# Sheet2.net
KiCad netlist of a schematic drawn in Altium Designer
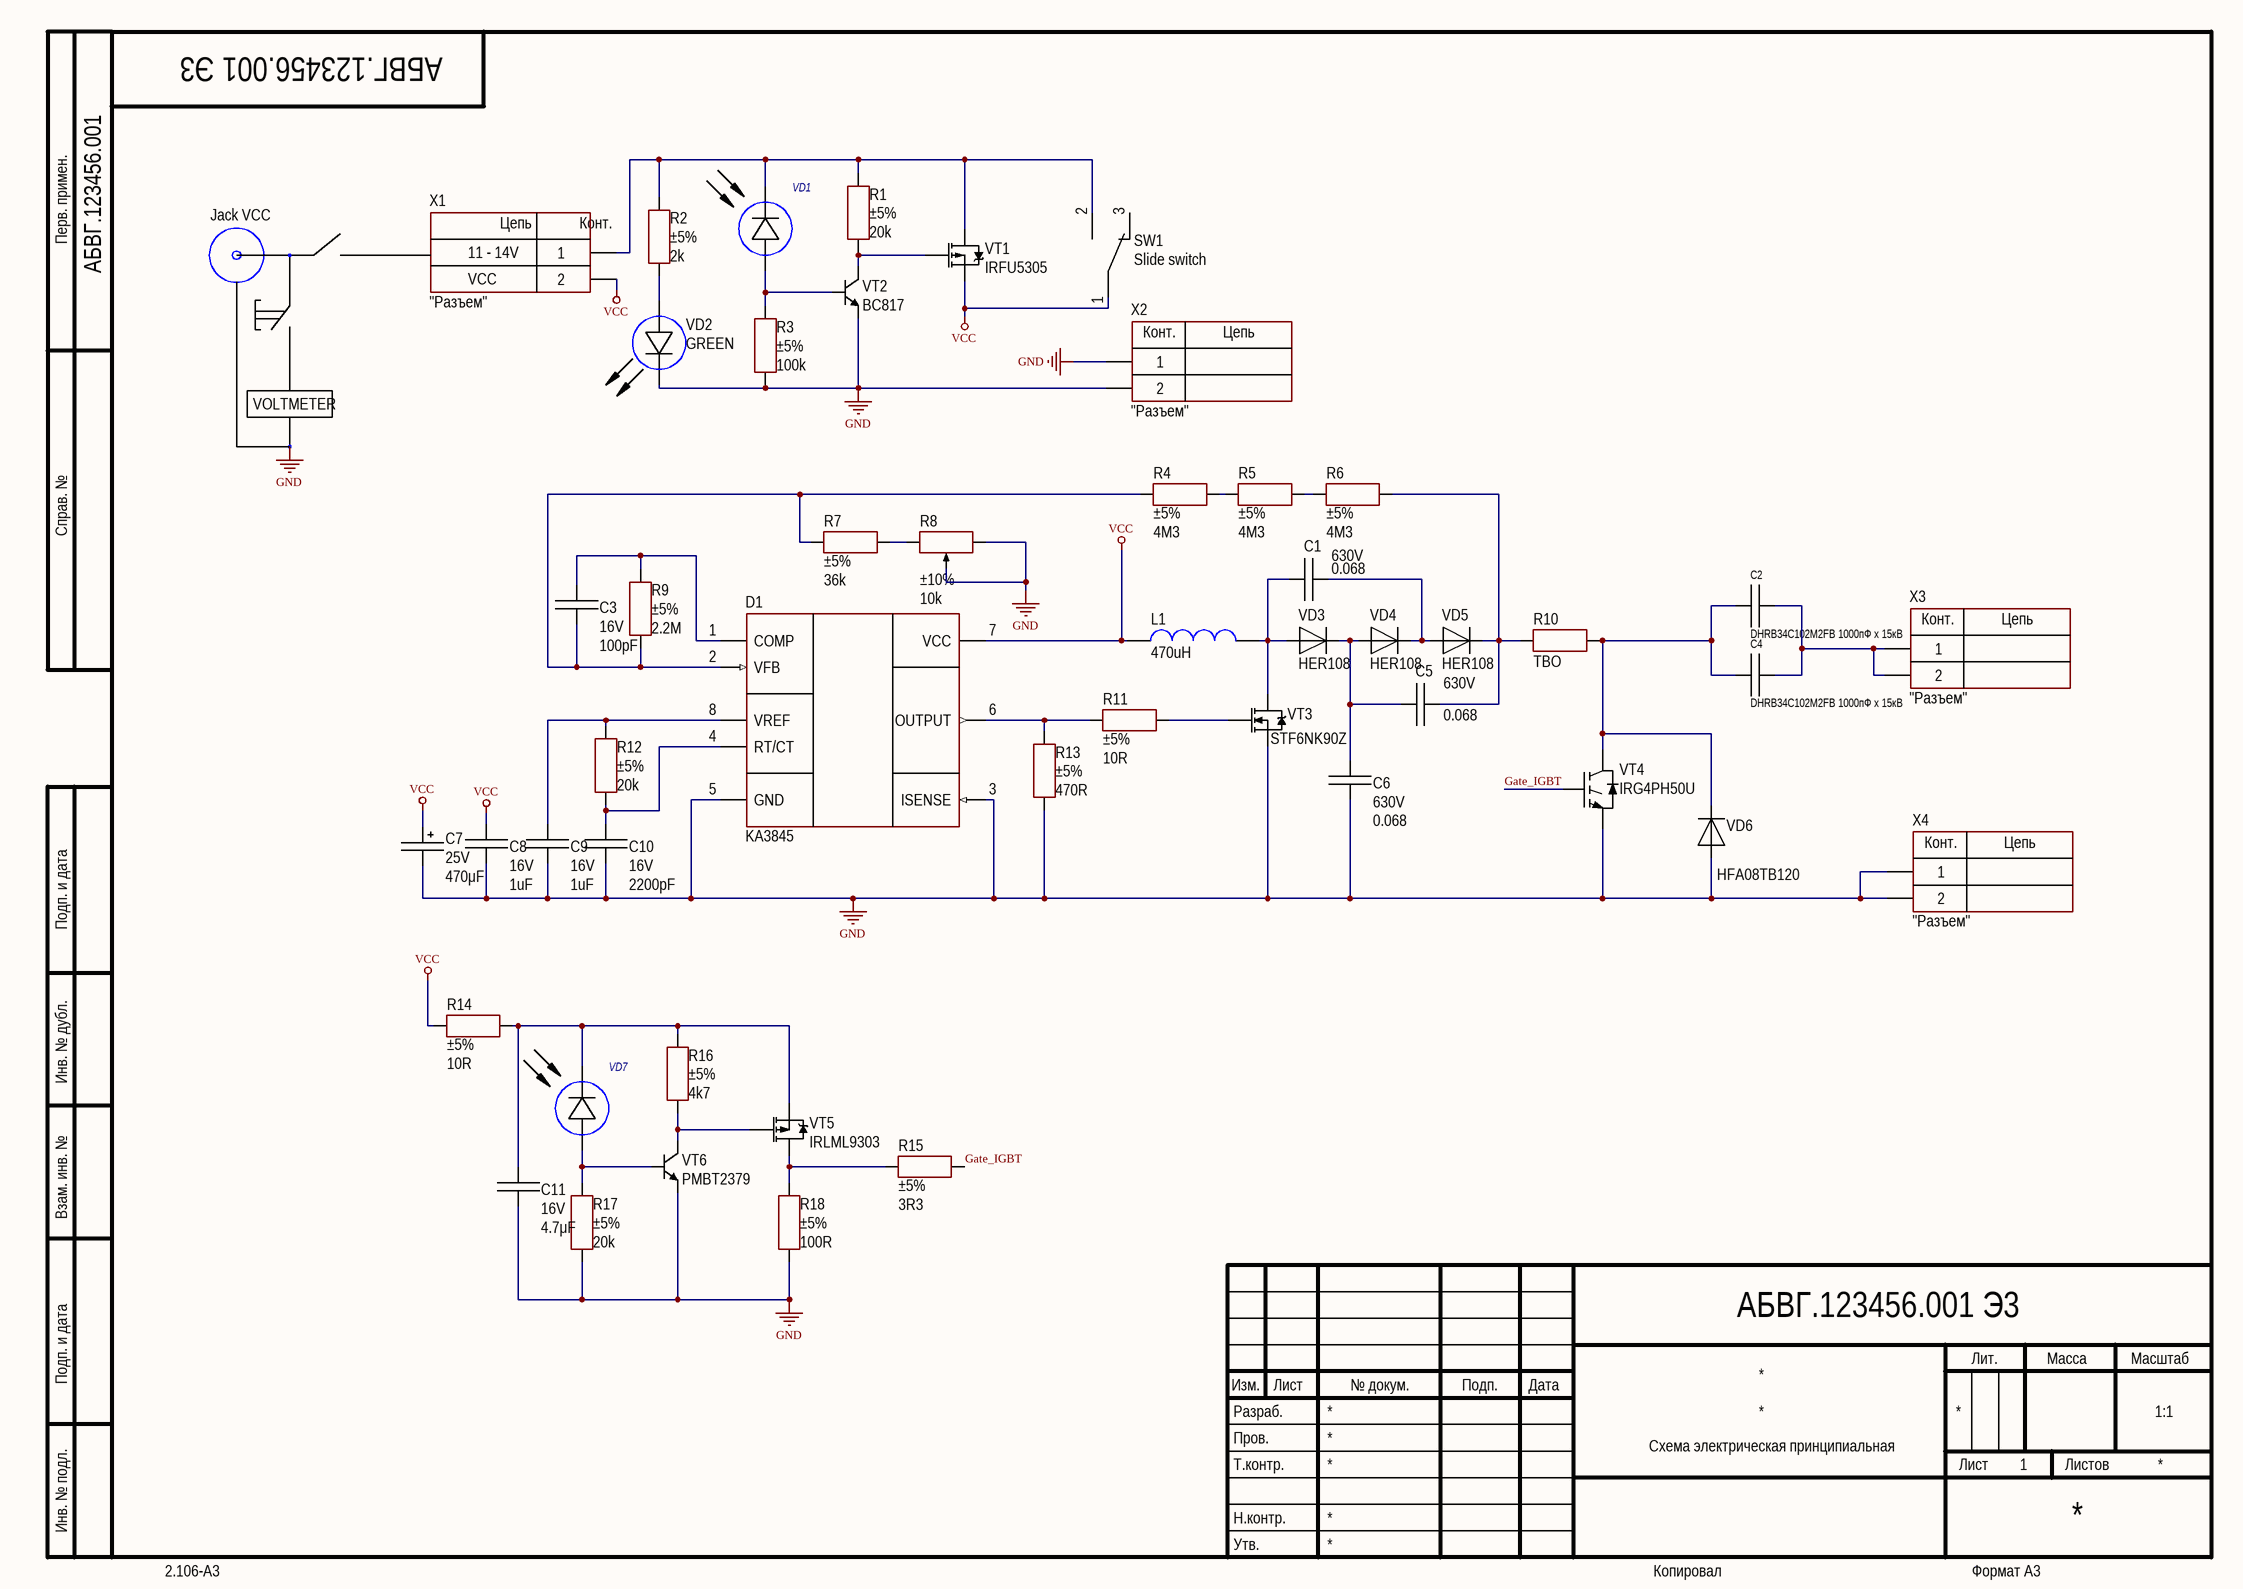
[diagram p0: Sheet2.SchDoc]

(export (version "E")
  (design (tool "Eeschema 10.0.6"))
  (components
    (comp (ref "C1")
      (value "0.068")
      (footprint "CAP: 1812")
      (fields
        (field (name "MANUFACTURER") "Yageo")
        (field (name "PARTNUMBER") "CC1812KKX7R9BB105")
        (field (name "VALUEMANUFACTURERPARTNUMBER") "Ceramic capacitor, 0.068, X7R, ±10%, 630V, 1812, -55...+125°C")
        (field (name "VOLTAGE") "630V")
      )
      (libsource (lib "") (part "Ceramic_1812_1"))
    )
    (comp (ref "C2")
      (value "DHRB34C102M2FB 1000пФ х 15кВ")
      (footprint "CAP: HV_CYL_METALL-PAPER_CAP")
      (libsource (lib "capacitor") (part "THROUGH_HOLE_CAP"))
    )
    (comp (ref "C3")
      (value "100pF")
      (footprint "CAP: 0805")
      (fields
        (field (name "MANUFACTURER") "Yageo")
        (field (name "PARTNUMBER") "CC0805KRX7R7BB104")
        (field (name "VALUEMANUFACTURERPARTNUMBER") "Ceramic capacitor, 100pF, X7R, ±10%, 16V, 0805, -55...+125°C")
        (field (name "VOLTAGE") "16V")
      )
      (libsource (lib "capacitor") (part "Ceramic_0805"))
    )
    (comp (ref "C4")
      (value "DHRB34C102M2FB 1000пФ х 15кВ")
      (footprint "CAP: HV_CYL_METALL-PAPER_CAP")
      (libsource (lib "capacitor") (part "THROUGH_HOLE_CAP"))
    )
    (comp (ref "C5")
      (value "0.068")
      (footprint "CAP: 1812")
      (fields
        (field (name "MANUFACTURER") "Yageo")
        (field (name "PARTNUMBER") "CC1812KKX7R9BB105")
        (field (name "VALUEMANUFACTURERPARTNUMBER") "Ceramic capacitor, 0.068, X7R, ±10%, 630V, 1812, -55...+125°C")
        (field (name "VOLTAGE") "630V")
      )
      (libsource (lib "capacitor") (part "Ceramic_1812"))
    )
    (comp (ref "C6")
      (value "0.068")
      (footprint "CAP: 1812")
      (fields
        (field (name "MANUFACTURER") "Yageo")
        (field (name "PARTNUMBER") "CC1812KKX7R9BB105")
        (field (name "VALUEMANUFACTURERPARTNUMBER") "Ceramic capacitor, 0.068, X7R, ±10%, 630V, 1812, -55...+125°C")
        (field (name "VOLTAGE") "630V")
      )
      (libsource (lib "") (part "Ceramic_1812_2"))
    )
    (comp (ref "C7")
      (value "470μF")
      (footprint "CAP: D8C3.5H12")
      (fields
        (field (name "MANUFACTURER") "Wurth")
        (field (name "PARTNUMBER") "860080475013")
        (field (name "VALUEMANUFACTURERPARTNUMBER") "Aluminium capacitor, 470μF, 25V, ±20%, 54mOhm, 14x10x5 mm, -55...+105°C")
        (field (name "VOLTAGE") "25V")
      )
      (libsource (lib "capacitor") (part "Aluminium"))
    )
    (comp (ref "C8")
      (value "1uF")
      (footprint "CAP: 0805")
      (fields
        (field (name "MANUFACTURER") "Yageo")
        (field (name "PARTNUMBER") "CC0805KRX7R7BB104")
        (field (name "VALUEMANUFACTURERPARTNUMBER") "Ceramic capacitor, 1uF, X7R, ±10%, 16V, 0805, -55...+125°C")
        (field (name "VOLTAGE") "16V")
      )
      (libsource (lib "capacitor") (part "Ceramic_0805"))
    )
    (comp (ref "C9")
      (value "1uF")
      (footprint "CAP: 0805")
      (fields
        (field (name "MANUFACTURER") "Yageo")
        (field (name "PARTNUMBER") "CC0805KRX7R7BB104")
        (field (name "VALUEMANUFACTURERPARTNUMBER") "Ceramic capacitor, 1uF, X7R, ±10%, 16V, 0805, -55...+125°C")
        (field (name "VOLTAGE") "16V")
      )
      (libsource (lib "capacitor") (part "Ceramic_0805"))
    )
    (comp (ref "C10")
      (value "2200pF")
      (footprint "CAP: 0805")
      (fields
        (field (name "MANUFACTURER") "Yageo")
        (field (name "PARTNUMBER") "CC0805KRX7R7BB104")
        (field (name "VALUEMANUFACTURERPARTNUMBER") "Ceramic capacitor, 2200pF, X7R, ±10%, 16V, 0805, -55...+125°C")
        (field (name "VOLTAGE") "16V")
      )
      (libsource (lib "capacitor") (part "Ceramic_0805"))
    )
    (comp (ref "C11")
      (value "4.7μF")
      (footprint "CAP: 0805")
      (fields
        (field (name "MANUFACTURER") "Yageo")
        (field (name "PARTNUMBER") "CC0805KRX7R7BB104")
        (field (name "VALUEMANUFACTURERPARTNUMBER") "Ceramic capacitor, 4.7μF, X7R, ±10%, 16V, 0805, -55...+125°C")
        (field (name "VOLTAGE") "16V")
      )
      (libsource (lib "capacitor") (part "Ceramic_0805"))
    )
    (comp (ref "D1")
      (value "~")
      (footprint "8-SOIC")
      (description "PWM controller")
      (fields
        (field (name "MANUFACTURER") "ON Semiconductor")
        (field (name "VALUEMANUFACTURERPARTNUMBER") "PWM controller, supply 10...30V, 500kHz, External switch, -40...+105°C, 8-SOIC")
        (field (name "PARTNUMBER") "KA3845")
      )
      (libsource (lib "ic-power-supply") (part "UC3842BVD1R2G"))
    )
    (comp (ref "L1")
      (value "470uH")
      (footprint "IND: DUMBELL 8.5x11x5")
      (libsource (lib "inductor") (part "Inductor_dumbbell"))
    )
    (comp (ref "R1")
      (value "20k")
      (footprint "RES: 0805")
      (fields
        (field (name "MANUFACTURER") "Yageo")
        (field (name "PARTNUMBER") "RC0805JR-07100RL")
        (field (name "VALUEMANUFACTURERPARTNUMBER") "Resistor film, 20k, ±5%, 0805, 0.125W, -55...+125°C")
        (field (name "TOLERANCE") "±5%")
      )
      (libsource (lib "resistor") (part "Resistor_0805"))
    )
    (comp (ref "R2")
      (value "2k")
      (footprint "RES: 0805")
      (fields
        (field (name "MANUFACTURER") "Yageo")
        (field (name "PARTNUMBER") "RC0805JR-07100RL")
        (field (name "VALUEMANUFACTURERPARTNUMBER") "Resistor film, 2k, ±5%, 0805, 0.125W, -55...+125°C")
        (field (name "TOLERANCE") "±5%")
      )
      (libsource (lib "") (part "Resistor_0805_3"))
    )
    (comp (ref "R3")
      (value "100k")
      (footprint "RES: 0805")
      (fields
        (field (name "MANUFACTURER") "Yageo")
        (field (name "PARTNUMBER") "RC0805JR-07100RL")
        (field (name "VALUEMANUFACTURERPARTNUMBER") "Resistor film, 100k, ±5%, 0805, 0.125W, -55...+125°C")
        (field (name "TOLERANCE") "±5%")
      )
      (libsource (lib "resistor") (part "Resistor_0805"))
    )
    (comp (ref "R4")
      (value "4M3")
      (footprint "RES: 1206")
      (fields
        (field (name "MANUFACTURER") "Yageo")
        (field (name "PARTNUMBER") "RC1206JR-07100RL")
        (field (name "VALUEMANUFACTURERPARTNUMBER") "Resistor film, 4M3, ±5%, 1206, 0.25W, -55...+125°C")
        (field (name "TOLERANCE") "±5%")
      )
      (libsource (lib "resistor") (part "Resistor_1206"))
    )
    (comp (ref "R5")
      (value "4M3")
      (footprint "RES: 1206")
      (fields
        (field (name "MANUFACTURER") "Yageo")
        (field (name "PARTNUMBER") "RC1206JR-07100RL")
        (field (name "VALUEMANUFACTURERPARTNUMBER") "Resistor film, 4M3, ±5%, 1206, 0.25W, -55...+125°C")
        (field (name "TOLERANCE") "±5%")
      )
      (libsource (lib "") (part "Resistor_1206_2"))
    )
    (comp (ref "R6")
      (value "4M3")
      (footprint "RES: 1206")
      (fields
        (field (name "MANUFACTURER") "Yageo")
        (field (name "PARTNUMBER") "RC1206JR-07100RL")
        (field (name "VALUEMANUFACTURERPARTNUMBER") "Resistor film, 4M3, ±5%, 1206, 0.25W, -55...+125°C")
        (field (name "TOLERANCE") "±5%")
      )
      (libsource (lib "") (part "Resistor_1206_2"))
    )
    (comp (ref "R7")
      (value "36k")
      (footprint "RES: 0805")
      (fields
        (field (name "MANUFACTURER") "Yageo")
        (field (name "PARTNUMBER") "RC0805JR-07100RL")
        (field (name "VALUEMANUFACTURERPARTNUMBER") "Resistor film, 36k, ±5%, 0805, 0.125W, -55...+125°C")
        (field (name "TOLERANCE") "±5%")
      )
      (libsource (lib "") (part "Resistor_0805_1"))
    )
    (comp (ref "R8")
      (value "10k")
      (footprint "RES: 3362P")
      (fields
        (field (name "MANUFACTURER") "Bourns")
        (field (name "PARTNUMBER") "3296W-1-103LF")
        (field (name "VALUEMANUFACTURERPARTNUMBER") "Resistor film, 10k, ±10%, 3296W, 0.5W, -55...+125°C")
        (field (name "TOLERANCE") "±10%")
      )
      (libsource (lib "resistor") (part "Trimmer"))
    )
    (comp (ref "R9")
      (value "2.2M")
      (footprint "RES: 0805")
      (fields
        (field (name "MANUFACTURER") "Yageo")
        (field (name "PARTNUMBER") "RC0805JR-07100RL")
        (field (name "VALUEMANUFACTURERPARTNUMBER") "Resistor film, 2.2M, ±5%, 0805, 0.125W, -55...+125°C")
        (field (name "TOLERANCE") "±5%")
      )
      (libsource (lib "resistor") (part "Resistor_0805"))
    )
    (comp (ref "R10")
      (value "ТВО")
      (footprint "RES: ТВО 0.5")
      (libsource (lib "resistor") (part "HV RESISTOR"))
    )
    (comp (ref "R11")
      (value "10R")
      (footprint "RES: 1206")
      (fields
        (field (name "MANUFACTURER") "Yageo")
        (field (name "PARTNUMBER") "RC1206JR-07100RL")
        (field (name "VALUEMANUFACTURERPARTNUMBER") "Resistor film, 10R, ±5%, 1206, 0.25W, -55...+125°C")
        (field (name "TOLERANCE") "±5%")
      )
      (libsource (lib "") (part "Resistor_1206_1"))
    )
    (comp (ref "R12")
      (value "20k")
      (footprint "RES: 0805")
      (fields
        (field (name "MANUFACTURER") "Yageo")
        (field (name "PARTNUMBER") "RC0805JR-07100RL")
        (field (name "VALUEMANUFACTURERPARTNUMBER") "Resistor film, 20k, ±5%, 0805, 0.125W, -55...+125°C")
        (field (name "TOLERANCE") "±5%")
      )
      (libsource (lib "resistor") (part "Resistor_0805"))
    )
    (comp (ref "R13")
      (value "470R")
      (footprint "RES: 0805")
      (fields
        (field (name "MANUFACTURER") "Yageo")
        (field (name "PARTNUMBER") "RC0805JR-07100RL")
        (field (name "VALUEMANUFACTURERPARTNUMBER") "Resistor film, 470R, ±5%, 0805, 0.125W, -55...+125°C")
        (field (name "TOLERANCE") "±5%")
      )
      (libsource (lib "") (part "Resistor_0805_2"))
    )
    (comp (ref "R14")
      (value "10R")
      (footprint "RES: 1206")
      (fields
        (field (name "MANUFACTURER") "Yageo")
        (field (name "PARTNUMBER") "RC1206JR-07100RL")
        (field (name "VALUEMANUFACTURERPARTNUMBER") "Resistor film, 10R, ±5%, 1206, 0.25W, -55...+125°C")
        (field (name "TOLERANCE") "±5%")
      )
      (libsource (lib "resistor") (part "Resistor_1206"))
    )
    (comp (ref "R15")
      (value "3R3")
      (footprint "RES: 1206")
      (fields
        (field (name "MANUFACTURER") "Yageo")
        (field (name "PARTNUMBER") "RC1206JR-07100RL")
        (field (name "VALUEMANUFACTURERPARTNUMBER") "Resistor film, 3R3, ±5%, 1206, 0.25W, -55...+125°C")
        (field (name "TOLERANCE") "±5%")
      )
      (libsource (lib "resistor") (part "Resistor_1206"))
    )
    (comp (ref "R16")
      (value "4k7")
      (footprint "RES: 0805")
      (fields
        (field (name "MANUFACTURER") "Yageo")
        (field (name "PARTNUMBER") "RC0805JR-07100RL")
        (field (name "VALUEMANUFACTURERPARTNUMBER") "Resistor film, 4k7, ±5%, 0805, 0.125W, -55...+125°C")
        (field (name "TOLERANCE") "±5%")
      )
      (libsource (lib "") (part "Resistor_0805_2"))
    )
    (comp (ref "R17")
      (value "20k")
      (footprint "RES: 0805")
      (fields
        (field (name "MANUFACTURER") "Yageo")
        (field (name "PARTNUMBER") "RC0805JR-07100RL")
        (field (name "VALUEMANUFACTURERPARTNUMBER") "Resistor film, 20k, ±5%, 0805, 0.125W, -55...+125°C")
        (field (name "TOLERANCE") "±5%")
      )
      (libsource (lib "") (part "Resistor_0805_2"))
    )
    (comp (ref "R18")
      (value "100R")
      (footprint "RES: 0805")
      (fields
        (field (name "MANUFACTURER") "Yageo")
        (field (name "PARTNUMBER") "RC0805JR-07100RL")
        (field (name "VALUEMANUFACTURERPARTNUMBER") "Resistor film, 100R, ±5%, 0805, 0.125W, -55...+125°C")
        (field (name "TOLERANCE") "±5%")
      )
      (libsource (lib "") (part "Resistor_0805_2"))
    )
    (comp (ref "SW1")
      (value "Slide switch")
      (footprint "SW: Slide_switch 3mm between outputs")
      (libsource (lib "electromechanics") (part "Slide_switch"))
    )
    (comp (ref "VD1") (value "SHF250") (footprint "LED: SFH757") (libsource (lib "diode") (part "SHF250")))
    (comp (ref "VD2")
      (value "~")
      (footprint "through component 5 mm")
      (fields
        (field (name "VALUEMANUFACTURERPARTNUMBER") "LED, Green, *, *, *, -55...+150°C")
        (field (name "COLOR") "GREEN")
      )
      (libsource (lib "diode") (part "LED_single"))
    )
    (comp (ref "VD3")
      (value "HER108")
      (footprint "DIODE: DO-41")
      (libsource (lib "diode") (part "Through_hole_single_diode"))
    )
    (comp (ref "VD4")
      (value "HER108")
      (footprint "DIODE: DO-41")
      (libsource (lib "diode") (part "Through_hole_single_diode"))
    )
    (comp (ref "VD5")
      (value "HER108")
      (footprint "DIODE: DO-41")
      (libsource (lib "diode") (part "Through_hole_single_diode"))
    )
    (comp (ref "VD6")
      (value "~")
      (footprint "TO220(D)")
      (fields
        (field (name "MANUFACTURER") "Micro Commercial")
        (field (name "VALUEMANUFACTURERPARTNUMBER") "Single diode, 75V, 150mA, 1V, 4ns, SOD-323, -55...+150°C")
        (field (name "VOLTAGE") "75V")
        (field (name "PARTNUMBER") "HFA08TB120")
      )
      (libsource (lib "diode") (part "Diode_single"))
    )
    (comp (ref "VD7") (value "SHF250") (footprint "LED: SFH757") (libsource (lib "diode") (part "SHF250")))
    (comp (ref "VT1")
      (value "~")
      (footprint "DPAK")
      (fields
        (field (name "MANUFACTURER") "Infineon Technologies")
        (field (name "VALUEMANUFACTURERPARTNUMBER") "MOSFET P-channel transistor, 20V, 2.6A, 2.9nC, 2.5W, 135mOhm, 220pF, SOT-23, -55...+150°C")
        (field (name "PARTNUMBER") "IRFU5305")
      )
      (libsource (lib "") (part "MOSFET_P_132_1"))
    )
    (comp (ref "VT2")
      (value "~")
      (footprint "SOT23")
      (fields
        (field (name "MANUFACTURER") "ON Semiconductor")
        (field (name "VALUEMANUFACTURERPARTNUMBER") "NPN transistor, 45V, 100mA, 100MHz, 300mW, 0.6V, 420, SOT-23, -55...+125°C")
        (field (name "PARTNUMBER") "BC817")
      )
      (libsource (lib "transistor") (part "BJT_NPN_132"))
    )
    (comp (ref "VT3")
      (value "~")
      (footprint "TO-220 HV")
      (fields
        (field (name "MANUFACTURER") "Infineon Technologies")
        (field (name "VALUEMANUFACTURERPARTNUMBER") "MOSFET N-channel transistor, 80V, 7A, 9.1nC, 2.5W, 34mOhm, 756pF, 8-TDSON, -55...+150°C")
        (field (name "PARTNUMBER") "STF6NK90Z")
      )
      (libsource (lib "transistor") (part "MOSFET_N_123"))
    )
    (comp (ref "VT4")
      (value "~")
      (footprint "TO247")
      (fields
        (field (name "MANUFACTURER") "Rohm Semiconductor")
        (field (name "VALUEMANUFACTURERPARTNUMBER") "IGBT transistor, 650V, 40A, 40nC, 144W, 2.1V, 22ns/73ns, TO247, -55...+125°C")
        (field (name "PARTNUMBER") "IRG4PH50U")
      )
      (libsource (lib "transistor") (part "IGBT"))
    )
    (comp (ref "VT5")
      (value "~")
      (footprint "SOT23")
      (fields
        (field (name "MANUFACTURER") "Infineon Technologies")
        (field (name "VALUEMANUFACTURERPARTNUMBER") "MOSFET P-channel transistor, 20V, 2.6A, 2.9nC, 2.5W, 135mOhm, 220pF, SOT-23, -55...+150°C")
        (field (name "PARTNUMBER") "IRLML9303")
      )
      (libsource (lib "transistor") (part "MOSFET_P_132"))
    )
    (comp (ref "VT6")
      (value "~")
      (footprint "SOT23")
      (fields
        (field (name "MANUFACTURER") "ON Semiconductor")
        (field (name "VALUEMANUFACTURERPARTNUMBER") "NPN transistor, 45V, 100mA, 100MHz, 300mW, 0.6V, 420, SOT-23, -55...+125°C")
        (field (name "PARTNUMBER") "PMBT2379")
      )
      (libsource (lib "transistor") (part "BJT_NPN_132"))
    )
    (comp (ref "X1")
      (value "~")
      (footprint "CON: KF301-5.0-2P")
      (fields
        (field (name "MANUFACTURER") "Degson")
        (field (name "VALUEMANUFACTURERPARTNUMBER") "Terminal connector, 2pin, 3.5mm, 300VAC, 10A")
        (field (name "PARTNUMBER") "DG350-3.5-02P-14")
        (field (name "COMMENTTEXT") "\"Разъем\"")
      )
      (libsource (lib "connector") (part "Connector_terminal_2pin"))
    )
    (comp (ref "X2")
      (value "~")
      (footprint "CON: KF301-5.0-2P")
      (fields
        (field (name "MANUFACTURER") "Degson")
        (field (name "VALUEMANUFACTURERPARTNUMBER") "Terminal connector, 2pin, 3.5mm, 300VAC, 10A")
        (field (name "PARTNUMBER") "DG350-3.5-02P-14")
        (field (name "COMMENTTEXT") "\"Разъем\"")
      )
      (libsource (lib "") (part "Connector_terminal_2pin_1"))
    )
    (comp (ref "X3")
      (value "~")
      (footprint "CON: KF301-5.0-2P")
      (fields
        (field (name "MANUFACTURER") "Degson")
        (field (name "VALUEMANUFACTURERPARTNUMBER") "Terminal connector, 2pin, 3.5mm, 300VAC, 10A")
        (field (name "PARTNUMBER") "DG350-3.5-02P-14")
        (field (name "COMMENTTEXT") "\"Разъем\"")
      )
      (libsource (lib "") (part "Connector_terminal_2pin_1"))
    )
    (comp (ref "X4")
      (value "~")
      (footprint "CON: KF301-5.0-2P")
      (fields
        (field (name "MANUFACTURER") "Degson")
        (field (name "VALUEMANUFACTURERPARTNUMBER") "Terminal connector, 2pin, 3.5mm, 300VAC, 10A")
        (field (name "PARTNUMBER") "DG350-3.5-02P-14")
        (field (name "COMMENTTEXT") "\"Разъем\"")
      )
      (libsource (lib "") (part "Connector_terminal_2pin_1"))
    )
  )
  (nets
    (net (code "1") (name "/Gate_IGBT") (class "Default")
      (node (ref "R15") (pin "2") (pinfunction "2_2") (pintype "passive"))
      (node (ref "VT4") (pin "1") (pinfunction "G_1") (pintype "passive"))
    )
    (net (code "2") (name "GND") (class "Default")
      (node (ref "C10") (pin "1") (pinfunction "1_1") (pintype "passive"))
      (node (ref "C11") (pin "1") (pinfunction "1_1") (pintype "passive"))
      (node (ref "C6") (pin "2") (pinfunction "2_2") (pintype "passive"))
      (node (ref "C7") (pin "2") (pinfunction "2_2") (pintype "passive"))
      (node (ref "C8") (pin "1") (pinfunction "1_1") (pintype "passive"))
      (node (ref "C9") (pin "1") (pinfunction "1_1") (pintype "passive"))
      (node (ref "D1") (pin "3") (pinfunction "ISENSE_3") (pintype "input"))
      (node (ref "D1") (pin "5") (pinfunction "GND_5") (pintype "passive"))
      (node (ref "R13") (pin "2") (pinfunction "2_2") (pintype "passive"))
      (node (ref "R17") (pin "2") (pinfunction "2_2") (pintype "passive"))
      (node (ref "R18") (pin "2") (pinfunction "2_2") (pintype "passive"))
      (node (ref "R3") (pin "1") (pinfunction "1_1") (pintype "passive"))
      (node (ref "R8") (pin "1") (pinfunction "1_1") (pintype "passive"))
      (node (ref "R8") (pin "2") (pinfunction "2_2") (pintype "passive"))
      (node (ref "VD2") (pin "2") (pinfunction "C_2") (pintype "passive"))
      (node (ref "VD6") (pin "1") (pinfunction "1_1") (pintype "passive"))
      (node (ref "VT2") (pin "2") (pinfunction "E_2") (pintype "passive"))
      (node (ref "VT3") (pin "3") (pinfunction "S_3") (pintype "passive"))
      (node (ref "VT4") (pin "3") (pinfunction "E_3") (pintype "passive"))
      (node (ref "VT6") (pin "2") (pinfunction "E_2") (pintype "passive"))
      (node (ref "X2") (pin "1") (pinfunction "1_1") (pintype "passive"))
      (node (ref "X2") (pin "2") (pinfunction "2_2") (pintype "passive"))
      (node (ref "X4") (pin "1") (pinfunction "1_1") (pintype "passive"))
      (node (ref "X4") (pin "2") (pinfunction "2_2") (pintype "passive"))
    )
    (net (code "3") (name "Net-(C1-Pad1)") (class "Default")
      (node (ref "C1") (pin "1") (pinfunction "1_1") (pintype "passive"))
      (node (ref "VD4") (pin "2") (pinfunction "2_2") (pintype "passive"))
      (node (ref "VD5") (pin "1") (pinfunction "1_1") (pintype "passive"))
    )
    (net (code "4") (name "Net-(C2-Pad1)") (class "Default")
      (node (ref "C2") (pin "1") (pinfunction "1_1") (pintype "passive"))
      (node (ref "C4") (pin "1") (pinfunction "1_1") (pintype "passive"))
      (node (ref "X3") (pin "1") (pinfunction "1_1") (pintype "passive"))
      (node (ref "X3") (pin "2") (pinfunction "2_2") (pintype "passive"))
    )
    (net (code "5") (name "Net-(C5-Pad1)") (class "Default")
      (node (ref "C5") (pin "1") (pinfunction "1_1") (pintype "passive"))
      (node (ref "R10") (pin "1") (pinfunction "1_1") (pintype "passive"))
      (node (ref "R6") (pin "2") (pinfunction "2_2") (pintype "passive"))
      (node (ref "VD5") (pin "2") (pinfunction "2_2") (pintype "passive"))
    )
    (net (code "6") (name "Net-(C5-Pad2)") (class "Default")
      (node (ref "C5") (pin "2") (pinfunction "2_2") (pintype "passive"))
      (node (ref "C6") (pin "1") (pinfunction "1_1") (pintype "passive"))
      (node (ref "VD3") (pin "2") (pinfunction "2_2") (pintype "passive"))
      (node (ref "VD4") (pin "1") (pinfunction "1_1") (pintype "passive"))
    )
    (net (code "7") (name "Net-(D1-COMP)") (class "Default")
      (node (ref "C3") (pin "2") (pinfunction "2_2") (pintype "passive"))
      (node (ref "D1") (pin "1") (pinfunction "COMP_1") (pintype "passive"))
      (node (ref "R9") (pin "2") (pinfunction "2_2") (pintype "passive"))
    )
    (net (code "8") (name "Net-(D1-OUTPUT)") (class "Default")
      (node (ref "D1") (pin "6") (pinfunction "OUTPUT_6") (pintype "output"))
      (node (ref "R11") (pin "2") (pinfunction "2_2") (pintype "passive"))
      (node (ref "R13") (pin "1") (pinfunction "1_1") (pintype "passive"))
    )
    (net (code "9") (name "Net-(D1-RT{slash}CT)") (class "Default")
      (node (ref "C10") (pin "2") (pinfunction "2_2") (pintype "passive"))
      (node (ref "D1") (pin "4") (pinfunction "RT/CT_4") (pintype "passive"))
      (node (ref "R12") (pin "1") (pinfunction "1_1") (pintype "passive"))
    )
    (net (code "10") (name "Net-(D1-VFB)") (class "Default")
      (node (ref "C3") (pin "1") (pinfunction "1_1") (pintype "passive"))
      (node (ref "D1") (pin "2") (pinfunction "VFB_2") (pintype "input"))
      (node (ref "R4") (pin "1") (pinfunction "1_1") (pintype "passive"))
      (node (ref "R7") (pin "2") (pinfunction "2_2") (pintype "passive"))
      (node (ref "R9") (pin "1") (pinfunction "1_1") (pintype "passive"))
    )
    (net (code "11") (name "Net-(D1-VREF)") (class "Default")
      (node (ref "C9") (pin "2") (pinfunction "2_2") (pintype "passive"))
      (node (ref "D1") (pin "8") (pinfunction "VREF_8") (pintype "passive"))
      (node (ref "R12") (pin "2") (pinfunction "2_2") (pintype "passive"))
    )
    (net (code "12") (name "Net-(R4-Pad2)") (class "Default")
      (node (ref "R4") (pin "2") (pinfunction "2_2") (pintype "passive"))
      (node (ref "R5") (pin "1") (pinfunction "1_1") (pintype "passive"))
    )
    (net (code "13") (name "Net-(R5-Pad2)") (class "Default")
      (node (ref "R5") (pin "2") (pinfunction "2_2") (pintype "passive"))
      (node (ref "R6") (pin "1") (pinfunction "1_1") (pintype "passive"))
    )
    (net (code "14") (name "Net-(R7-Pad1)") (class "Default")
      (node (ref "R7") (pin "1") (pinfunction "1_1") (pintype "passive"))
      (node (ref "R8") (pin "3") (pinfunction "3_3") (pintype "passive"))
    )
    (net (code "15") (name "Net-(VD1-A)") (class "Default")
      (node (ref "R3") (pin "2") (pinfunction "2_2") (pintype "passive"))
      (node (ref "VD1") (pin "1") (pinfunction "A_1") (pintype "passive"))
      (node (ref "VT2") (pin "1") (pinfunction "B_1") (pintype "passive"))
    )
    (net (code "16") (name "Net-(VD1-C)") (class "Default")
      (node (ref "R1") (pin "2") (pinfunction "2_2") (pintype "passive"))
      (node (ref "R2") (pin "2") (pinfunction "2_2") (pintype "passive"))
      (node (ref "SW1") (pin "2") (pinfunction "4_2") (pintype "passive"))
      (node (ref "VD1") (pin "2") (pinfunction "C_2") (pintype "passive"))
      (node (ref "VT1") (pin "3") (pinfunction "D_3") (pintype "passive"))
      (node (ref "X1") (pin "1") (pinfunction "1_1") (pintype "passive"))
    )
    (net (code "17") (name "Net-(VD2-A)") (class "Default")
      (node (ref "R2") (pin "1") (pinfunction "1_1") (pintype "passive"))
      (node (ref "VD2") (pin "1") (pinfunction "A_1") (pintype "passive"))
    )
    (net (code "18") (name "Net-(VD7-A)") (class "Default")
      (node (ref "R17") (pin "1") (pinfunction "1_1") (pintype "passive"))
      (node (ref "VD7") (pin "1") (pinfunction "A_1") (pintype "passive"))
      (node (ref "VT6") (pin "1") (pinfunction "B_1") (pintype "passive"))
    )
    (net (code "19") (name "Net-(VD7-C)") (class "Default")
      (node (ref "C11") (pin "2") (pinfunction "2_2") (pintype "passive"))
      (node (ref "R14") (pin "2") (pinfunction "2_2") (pintype "passive"))
      (node (ref "R16") (pin "1") (pinfunction "1_1") (pintype "passive"))
      (node (ref "VD7") (pin "2") (pinfunction "C_2") (pintype "passive"))
      (node (ref "VT5") (pin "2") (pinfunction "S_2") (pintype "passive"))
    )
    (net (code "20") (name "Net-(VT1-G)") (class "Default")
      (node (ref "R1") (pin "1") (pinfunction "1_1") (pintype "passive"))
      (node (ref "VT1") (pin "1") (pinfunction "G_1") (pintype "passive"))
      (node (ref "VT2") (pin "3") (pinfunction "C_3") (pintype "passive"))
    )
    (net (code "21") (name "Net-(VT3-D)") (class "Default")
      (node (ref "C1") (pin "2") (pinfunction "2_2") (pintype "passive"))
      (node (ref "L1") (pin "1") (pinfunction "1_1") (pintype "passive"))
      (node (ref "VD3") (pin "1") (pinfunction "1_1") (pintype "passive"))
      (node (ref "VT3") (pin "2") (pinfunction "D_2") (pintype "passive"))
    )
    (net (code "22") (name "Net-(VT3-G)") (class "Default")
      (node (ref "R11") (pin "1") (pinfunction "1_1") (pintype "passive"))
      (node (ref "VT3") (pin "1") (pinfunction "G_1") (pintype "passive"))
    )
    (net (code "23") (name "Net-(VT4-C)") (class "Default")
      (node (ref "C2") (pin "2") (pinfunction "2_2") (pintype "passive"))
      (node (ref "C4") (pin "2") (pinfunction "2_2") (pintype "passive"))
      (node (ref "R10") (pin "2") (pinfunction "2_2") (pintype "passive"))
      (node (ref "VD6") (pin "2") (pinfunction "2_2") (pintype "passive"))
      (node (ref "VT4") (pin "2") (pinfunction "C_2") (pintype "passive"))
    )
    (net (code "24") (name "Net-(VT5-D)") (class "Default")
      (node (ref "R15") (pin "1") (pinfunction "1_1") (pintype "passive"))
      (node (ref "R18") (pin "1") (pinfunction "1_1") (pintype "passive"))
      (node (ref "VT5") (pin "3") (pinfunction "D_3") (pintype "passive"))
    )
    (net (code "25") (name "Net-(VT5-G)") (class "Default")
      (node (ref "R16") (pin "2") (pinfunction "2_2") (pintype "passive"))
      (node (ref "VT5") (pin "1") (pinfunction "G_1") (pintype "passive"))
      (node (ref "VT6") (pin "3") (pinfunction "C_3") (pintype "passive"))
    )
    (net (code "26") (name "VCC") (class "Default")
      (node (ref "C7") (pin "1") (pinfunction "1_1") (pintype "passive"))
      (node (ref "C8") (pin "2") (pinfunction "2_2") (pintype "passive"))
      (node (ref "D1") (pin "7") (pinfunction "VCC_7") (pintype "passive"))
      (node (ref "L1") (pin "2") (pinfunction "2_2") (pintype "passive"))
      (node (ref "R14") (pin "1") (pinfunction "1_1") (pintype "passive"))
      (node (ref "SW1") (pin "1") (pinfunction "3_1") (pintype "passive"))
      (node (ref "VT1") (pin "2") (pinfunction "S_2") (pintype "passive"))
      (node (ref "X1") (pin "2") (pinfunction "2_2") (pintype "passive"))
    )
    (net (code "27") (name "unconnected-(SW1-4-Pad3)") (class "Default")
      (node (ref "SW1") (pin "3") (pinfunction "4_3") (pintype "passive"))
    )
  )
)
